# routev9_1.net
KiCad netlist of a schematic drawn in EAGLE
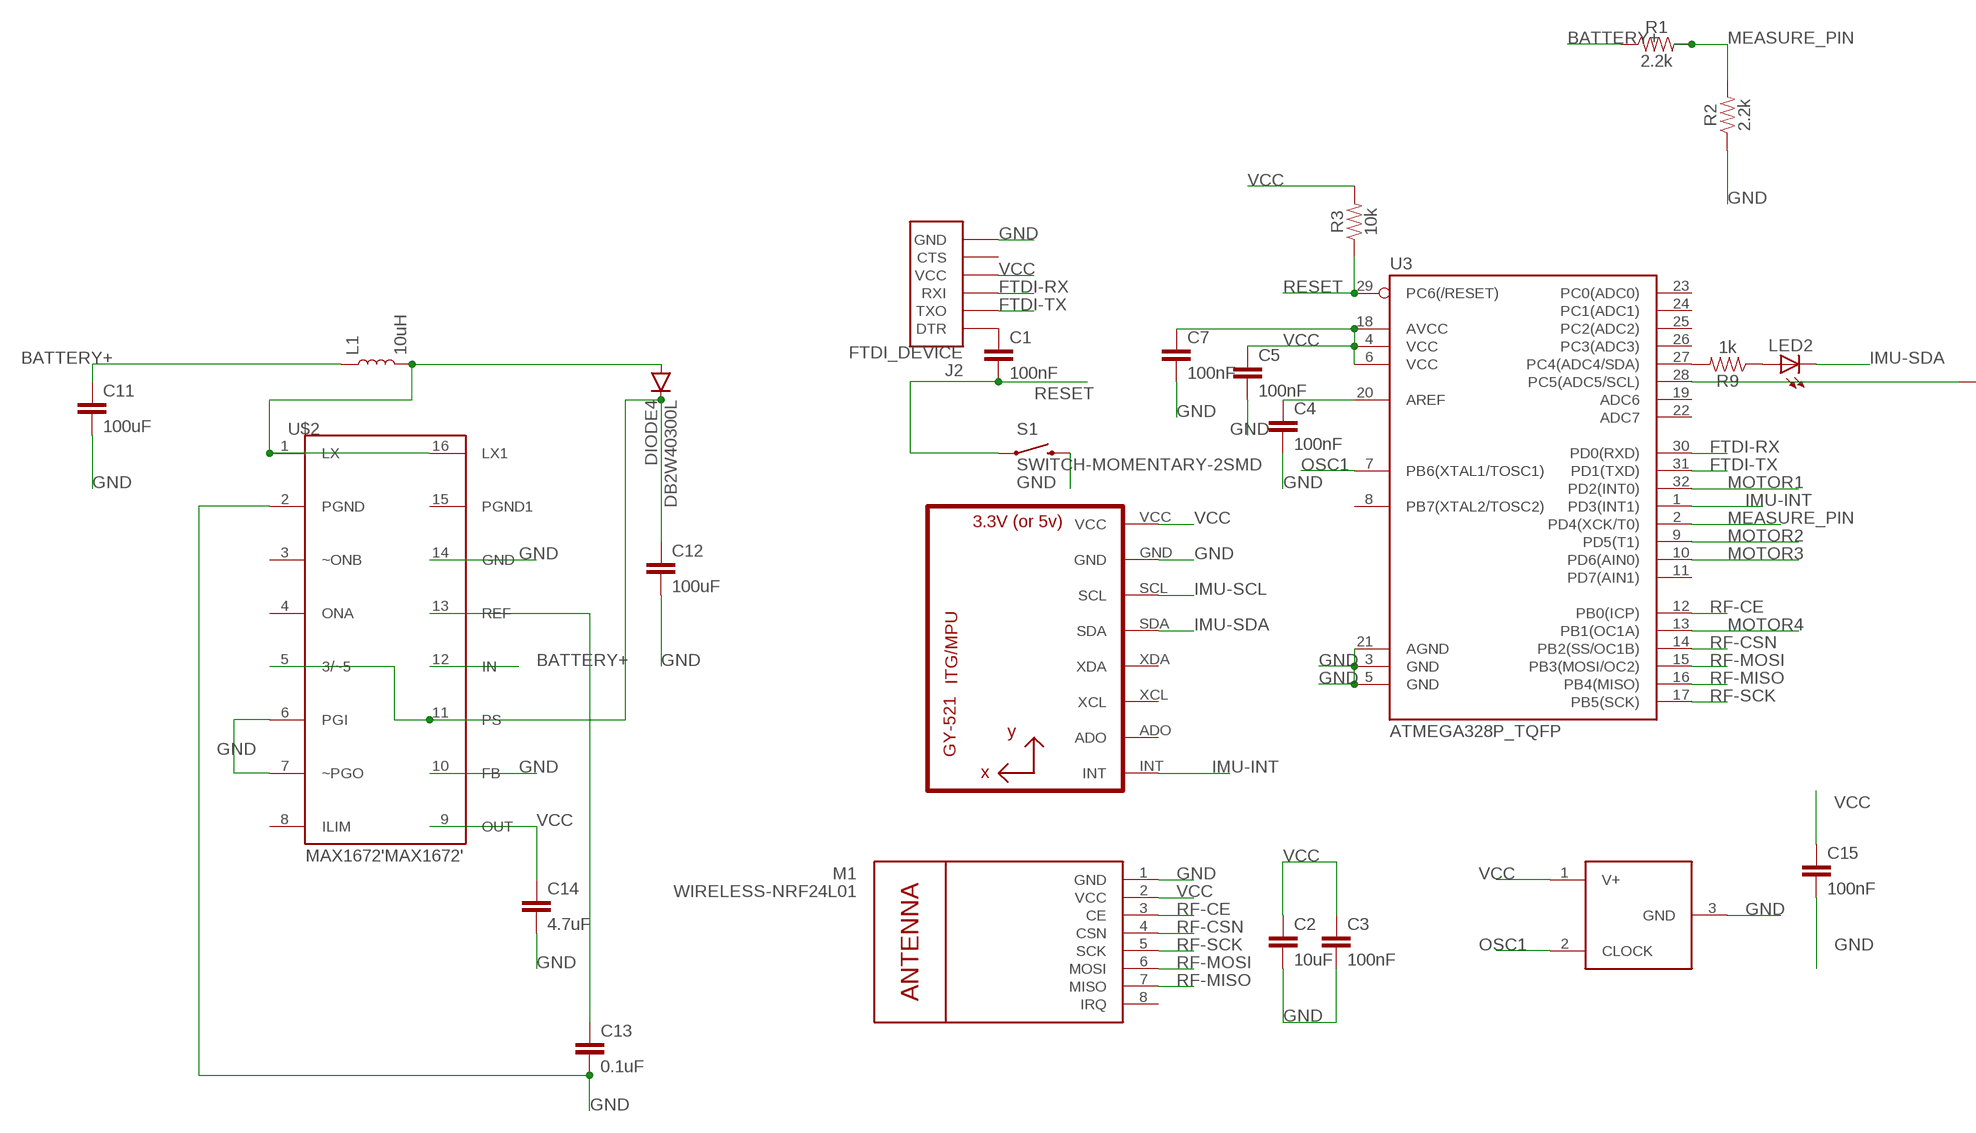
[diagram p0: schematic, sheet 1, part 1 of 2]
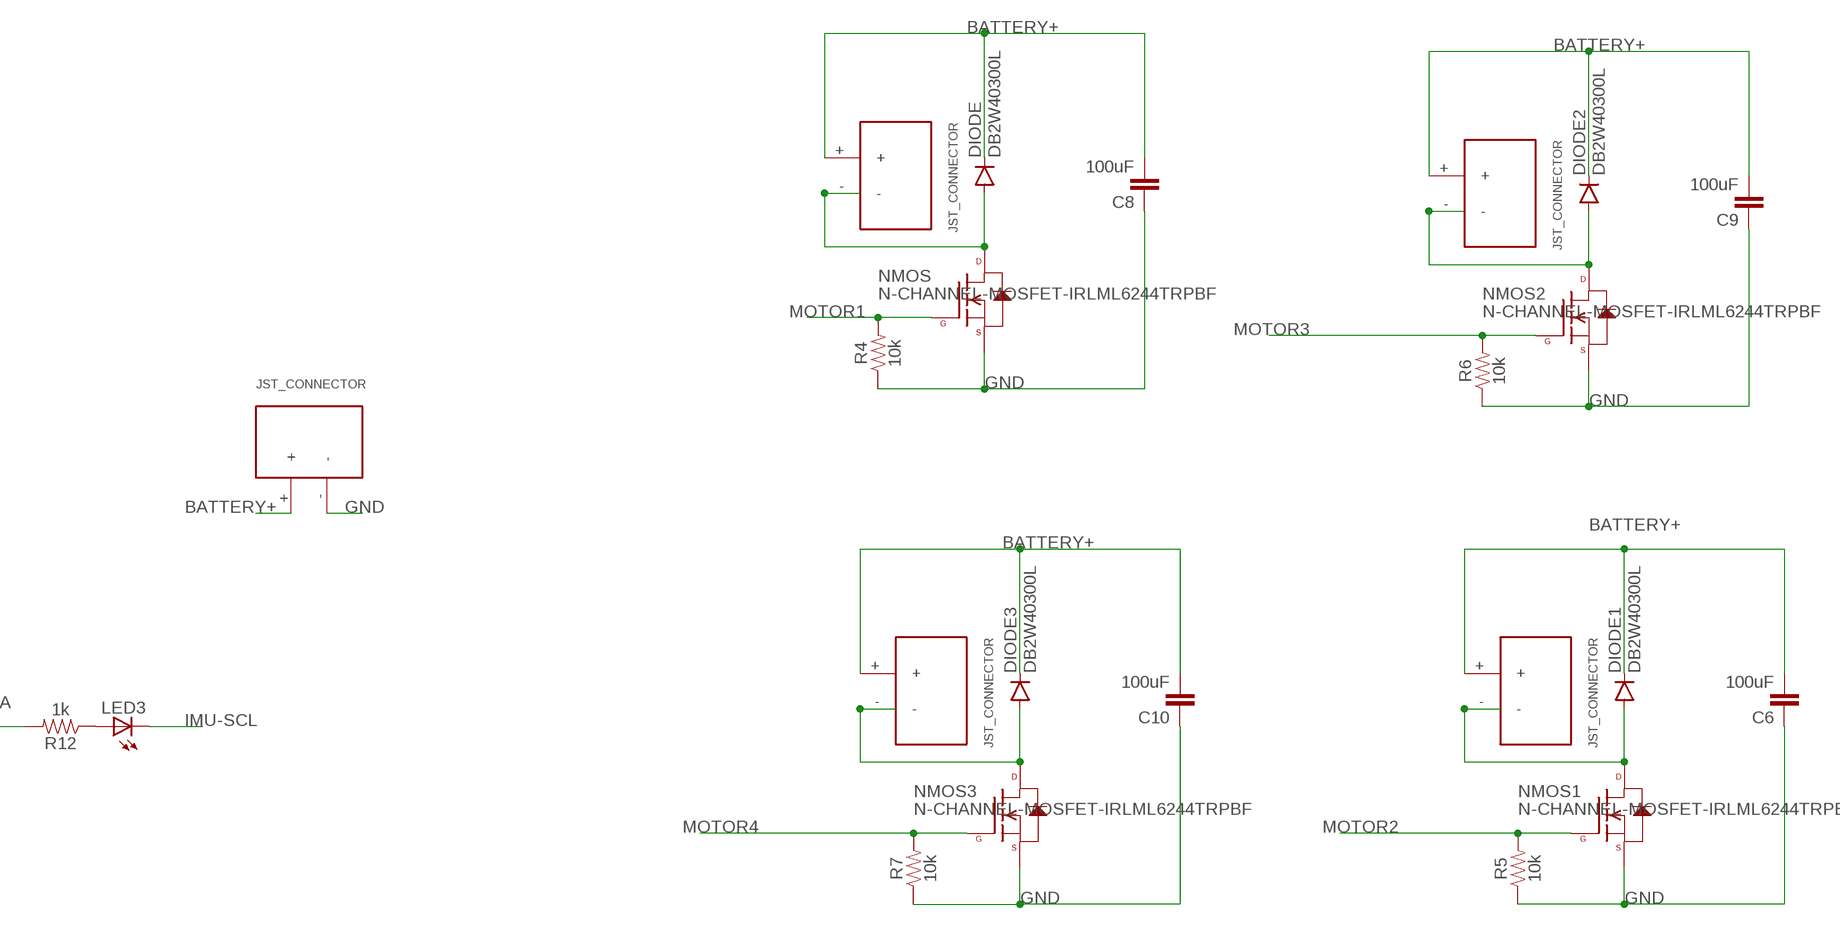
[diagram p1: schematic, sheet 1, part 2 of 2]

(export (version "E")
  (design (tool "Eeschema 10.0.6"))
  (components
    (comp (ref "AXR1")
      (value "MAX7375")
      (footprint "eagle-import:SC70-3L")
      (libsource (lib "eagle-import") (part "MAX7375"))
    )
    (comp (ref "C1")
      (value "100nF")
      (footprint "eagle-import:0603-CAP")
      (libsource (lib "eagle-import") (part "0.1UF-25V(+80/-20%)(0603)"))
    )
    (comp (ref "C2")
      (value "10uF")
      (footprint "eagle-import:0603-CAP")
      (libsource (lib "eagle-import") (part "CAP0603-CAP"))
    )
    (comp (ref "C3")
      (value "100nF")
      (footprint "eagle-import:0603-CAP")
      (libsource (lib "eagle-import") (part "CAP0603-CAP"))
    )
    (comp (ref "C4")
      (value "100nF")
      (footprint "eagle-import:0603-CAP")
      (libsource (lib "eagle-import") (part "CAP0603-CAP"))
    )
    (comp (ref "C5")
      (value "100nF")
      (footprint "eagle-import:0603-CAP")
      (libsource (lib "eagle-import") (part "CAP0603-CAP"))
    )
    (comp (ref "C6")
      (value "100uF")
      (footprint "eagle-import:0603-CAP")
      (libsource (lib "eagle-import") (part "CAP0603-CAP"))
    )
    (comp (ref "C7")
      (value "100nF")
      (footprint "eagle-import:0603-CAP")
      (libsource (lib "eagle-import") (part "CAP0603-CAP"))
    )
    (comp (ref "C8")
      (value "100uF")
      (footprint "eagle-import:0603-CAP")
      (libsource (lib "eagle-import") (part "CAP0603-CAP"))
    )
    (comp (ref "C9")
      (value "100uF")
      (footprint "eagle-import:0603-CAP")
      (libsource (lib "eagle-import") (part "CAP0603-CAP"))
    )
    (comp (ref "C10")
      (value "100uF")
      (footprint "eagle-import:0603-CAP")
      (libsource (lib "eagle-import") (part "CAP0603-CAP"))
    )
    (comp (ref "C11")
      (value "100uF")
      (footprint "eagle-import:0603-CAP")
      (libsource (lib "eagle-import") (part "CAP0603-CAP"))
    )
    (comp (ref "C12")
      (value "100uF")
      (footprint "eagle-import:0603-CAP")
      (libsource (lib "eagle-import") (part "CAP0603-CAP"))
    )
    (comp (ref "C13")
      (value "0.1uF")
      (footprint "eagle-import:0603-CAP")
      (libsource (lib "eagle-import") (part "CAP0603-CAP"))
    )
    (comp (ref "C14")
      (value "4.7uF")
      (footprint "eagle-import:0603-CAP")
      (libsource (lib "eagle-import") (part "CAP0603-CAP"))
    )
    (comp (ref "C15")
      (value "100nF")
      (footprint "eagle-import:0603-CAP")
      (libsource (lib "eagle-import") (part "0.1UF-25V(+80/-20%)(0603)"))
    )
    (comp (ref "DIODE")
      (value "DB2W40300L")
      (footprint "eagle-import:MINI2-F3-B")
      (libsource (lib "eagle-import") (part "DB2W40300L"))
    )
    (comp (ref "DIODE1")
      (value "DB2W40300L")
      (footprint "eagle-import:MINI2-F3-B")
      (libsource (lib "eagle-import") (part "DB2W40300L"))
    )
    (comp (ref "DIODE2")
      (value "DB2W40300L")
      (footprint "eagle-import:MINI2-F3-B")
      (libsource (lib "eagle-import") (part "DB2W40300L"))
    )
    (comp (ref "DIODE3")
      (value "DB2W40300L")
      (footprint "eagle-import:MINI2-F3-B")
      (libsource (lib "eagle-import") (part "DB2W40300L"))
    )
    (comp (ref "DIODE4")
      (value "DB2W40300L")
      (footprint "eagle-import:MINI2-F3-B")
      (libsource (lib "eagle-import") (part "DB2W40300L"))
    )
    (comp (ref "J2")
      (value "FTDI_DEVICE")
      (footprint "eagle-import:FTDI_DEVICE_SIDE")
      (libsource (lib "eagle-import") (part "FTDI_DEVICE"))
    )
    (comp (ref "L1")
      (value "10uH")
      (footprint "eagle-import:0603")
      (libsource (lib "eagle-import") (part "INDUCTOR-0603-33NH"))
    )
    (comp (ref "LED2")
      (value "LED0603")
      (footprint "eagle-import:LED-0603")
      (libsource (lib "eagle-import") (part "LED0603"))
    )
    (comp (ref "LED3")
      (value "LED0603")
      (footprint "eagle-import:LED-0603")
      (libsource (lib "eagle-import") (part "LED0603"))
    )
    (comp (ref "M1")
      (value "WIRELESS-NRF24L01")
      (footprint "eagle-import:WIRELESS-NRF24L01")
      (libsource (lib "eagle-import") (part "WIRELESS-NRF24L01"))
    )
    (comp (ref "MOTOR")
      (value "JST_CONNECTOR_FEMALE")
      (footprint "eagle-import:JST_CONNECTOR_FEMALE")
      (libsource (lib "eagle-import") (part "JST_CONNECTOR_FEMALE"))
    )
    (comp (ref "MOTOR1")
      (value "JST_CONNECTOR_FEMALE")
      (footprint "eagle-import:JST_CONNECTOR_FEMALE")
      (libsource (lib "eagle-import") (part "JST_CONNECTOR_FEMALE"))
    )
    (comp (ref "MOTOR2")
      (value "JST_CONNECTOR_FEMALE")
      (footprint "eagle-import:JST_CONNECTOR_FEMALE")
      (libsource (lib "eagle-import") (part "JST_CONNECTOR_FEMALE"))
    )
    (comp (ref "MOTOR3")
      (value "JST_CONNECTOR_FEMALE")
      (footprint "eagle-import:JST_CONNECTOR_FEMALE")
      (libsource (lib "eagle-import") (part "JST_CONNECTOR_FEMALE"))
    )
    (comp (ref "NMOS")
      (value "N-CHANNEL-MOSFET-IRLML6244TRPBF")
      (footprint "eagle-import:SOT23-3")
      (libsource (lib "eagle-import") (part "N-CHANNEL-MOSFET-IRLML6244TRPBF"))
    )
    (comp (ref "NMOS1")
      (value "N-CHANNEL-MOSFET-IRLML6244TRPBF")
      (footprint "eagle-import:SOT23-3")
      (libsource (lib "eagle-import") (part "N-CHANNEL-MOSFET-IRLML6244TRPBF"))
    )
    (comp (ref "NMOS2")
      (value "N-CHANNEL-MOSFET-IRLML6244TRPBF")
      (footprint "eagle-import:SOT23-3")
      (libsource (lib "eagle-import") (part "N-CHANNEL-MOSFET-IRLML6244TRPBF"))
    )
    (comp (ref "NMOS3")
      (value "N-CHANNEL-MOSFET-IRLML6244TRPBF")
      (footprint "eagle-import:SOT23-3")
      (libsource (lib "eagle-import") (part "N-CHANNEL-MOSFET-IRLML6244TRPBF"))
    )
    (comp (ref "R1")
      (value "2.2k")
      (footprint "eagle-import:0603")
      (libsource (lib "eagle-import") (part "2.2KOHM-0603-1/10W-1%"))
    )
    (comp (ref "R2")
      (value "2.2k")
      (footprint "eagle-import:0603")
      (libsource (lib "eagle-import") (part "2.2KOHM-0603-1/10W-1%"))
    )
    (comp (ref "R3")
      (value "10k")
      (footprint "eagle-import:0603")
      (libsource (lib "eagle-import") (part "2.2KOHM-0603-1/10W-1%"))
    )
    (comp (ref "R4")
      (value "10k")
      (footprint "eagle-import:0603")
      (libsource (lib "eagle-import") (part "2.2KOHM-0603-1/10W-1%"))
    )
    (comp (ref "R5")
      (value "10k")
      (footprint "eagle-import:0603")
      (libsource (lib "eagle-import") (part "2.2KOHM-0603-1/10W-1%"))
    )
    (comp (ref "R6")
      (value "10k")
      (footprint "eagle-import:0603")
      (libsource (lib "eagle-import") (part "2.2KOHM-0603-1/10W-1%"))
    )
    (comp (ref "R7")
      (value "10k")
      (footprint "eagle-import:0603")
      (libsource (lib "eagle-import") (part "2.2KOHM-0603-1/10W-1%"))
    )
    (comp (ref "R9")
      (value "1k")
      (footprint "eagle-import:0603")
      (libsource (lib "eagle-import") (part "2.2KOHM-0603-1/10W-1%"))
    )
    (comp (ref "R12")
      (value "1k")
      (footprint "eagle-import:0603")
      (libsource (lib "eagle-import") (part "2.2KOHM-0603-1/10W-1%"))
    )
    (comp (ref "S1")
      (value "SWITCH-MOMENTARY-2SMD")
      (footprint "eagle-import:TACTILE-SWITCH-SMD")
      (libsource (lib "eagle-import") (part "SWITCH-MOMENTARY-2SMD"))
    )
    (comp (ref "U$1")
      (value "JST_CONNECTOR_FEMALE")
      (footprint "eagle-import:JST_CONNECTOR_FEMALE")
      (libsource (lib "eagle-import") (part "JST_CONNECTOR_FEMALE"))
    )
    (comp (ref "U$2")
      (value "MAX1672'MAX1672'")
      (footprint "eagle-import:21-0055H_16")
      (libsource (lib "eagle-import") (part "MAX1672'MAX1672'"))
    )
    (comp (ref "U2")
      (value "GY-521MPU6050")
      (footprint "eagle-import:GY-521")
      (libsource (lib "eagle-import") (part "GY-521MPU6050"))
    )
    (comp (ref "U3")
      (value "ATMEGA328P_TQFP")
      (footprint "eagle-import:TQFP32-08")
      (libsource (lib "eagle-import") (part "ATMEGA328P_TQFP"))
    )
  )
  (nets
    (net (code "1") (name "BATTERY+") (class "Default")
      (node (ref "C10") (pin "2") (pinfunction "2_2") (pintype "passive"))
      (node (ref "C11") (pin "1") (pinfunction "1_1") (pintype "passive"))
      (node (ref "C6") (pin "2") (pinfunction "2_2") (pintype "passive"))
      (node (ref "C8") (pin "2") (pinfunction "2_2") (pintype "passive"))
      (node (ref "C9") (pin "2") (pinfunction "2_2") (pintype "passive"))
      (node (ref "DIODE") (pin "NEG") (pinfunction "GPIN_NEG") (pintype "passive"))
      (node (ref "DIODE1") (pin "NEG") (pinfunction "GPIN_NEG") (pintype "passive"))
      (node (ref "DIODE2") (pin "NEG") (pinfunction "GPIN_NEG") (pintype "passive"))
      (node (ref "DIODE3") (pin "NEG") (pinfunction "GPIN_NEG") (pintype "passive"))
      (node (ref "L1") (pin "1") (pinfunction "1_1") (pintype "passive"))
      (node (ref "MOTOR") (pin "+") (pinfunction "+_+") (pintype "bidirectional"))
      (node (ref "MOTOR1") (pin "+") (pinfunction "+_+") (pintype "bidirectional"))
      (node (ref "MOTOR2") (pin "+") (pinfunction "+_+") (pintype "bidirectional"))
      (node (ref "MOTOR3") (pin "+") (pinfunction "+_+") (pintype "bidirectional"))
      (node (ref "R1") (pin "1") (pinfunction "1_1") (pintype "passive"))
      (node (ref "U$1") (pin "+") (pinfunction "+_+") (pintype "bidirectional"))
      (node (ref "U$2") (pin "12") (pinfunction "IN_12") (pintype "bidirectional"))
    )
    (net (code "2") (name "FTDI-RX") (class "Default")
      (node (ref "J2") (pin "P$3") (pinfunction "RXI_P$3") (pintype "bidirectional"))
      (node (ref "U3") (pin "30") (pinfunction "PD0(RXD)_30") (pintype "bidirectional"))
    )
    (net (code "3") (name "FTDI-TX") (class "Default")
      (node (ref "J2") (pin "P$2") (pinfunction "TXO_P$2") (pintype "bidirectional"))
      (node (ref "U3") (pin "31") (pinfunction "PD1(TXD)_31") (pintype "bidirectional"))
    )
    (net (code "4") (name "GND") (class "Default")
      (node (ref "AXR1") (pin "3") (pinfunction "GND_3") (pintype "bidirectional"))
      (node (ref "C10") (pin "1") (pinfunction "1_1") (pintype "passive"))
      (node (ref "C11") (pin "2") (pinfunction "2_2") (pintype "passive"))
      (node (ref "C12") (pin "2") (pinfunction "2_2") (pintype "passive"))
      (node (ref "C13") (pin "2") (pinfunction "2_2") (pintype "passive"))
      (node (ref "C14") (pin "2") (pinfunction "2_2") (pintype "passive"))
      (node (ref "C15") (pin "2") (pinfunction "2_2") (pintype "passive"))
      (node (ref "C2") (pin "2") (pinfunction "2_2") (pintype "passive"))
      (node (ref "C3") (pin "2") (pinfunction "2_2") (pintype "passive"))
      (node (ref "C4") (pin "2") (pinfunction "2_2") (pintype "passive"))
      (node (ref "C5") (pin "2") (pinfunction "2_2") (pintype "passive"))
      (node (ref "C6") (pin "1") (pinfunction "1_1") (pintype "passive"))
      (node (ref "C7") (pin "2") (pinfunction "2_2") (pintype "passive"))
      (node (ref "C8") (pin "1") (pinfunction "1_1") (pintype "passive"))
      (node (ref "C9") (pin "1") (pinfunction "1_1") (pintype "passive"))
      (node (ref "J2") (pin "P$6") (pinfunction "GND_P$6") (pintype "bidirectional"))
      (node (ref "M1") (pin "1") (pinfunction "GND_1") (pintype "power_in"))
      (node (ref "NMOS") (pin "2") (pinfunction "S_2") (pintype "passive"))
      (node (ref "NMOS1") (pin "2") (pinfunction "S_2") (pintype "passive"))
      (node (ref "NMOS2") (pin "2") (pinfunction "S_2") (pintype "passive"))
      (node (ref "NMOS3") (pin "2") (pinfunction "S_2") (pintype "passive"))
      (node (ref "R2") (pin "1") (pinfunction "1_1") (pintype "passive"))
      (node (ref "R4") (pin "1") (pinfunction "1_1") (pintype "passive"))
      (node (ref "R5") (pin "1") (pinfunction "1_1") (pintype "passive"))
      (node (ref "R6") (pin "1") (pinfunction "1_1") (pintype "passive"))
      (node (ref "R7") (pin "1") (pinfunction "1_1") (pintype "passive"))
      (node (ref "S1") (pin "3") (pinfunction "2_3") (pintype "passive"))
      (node (ref "U$1") (pin "-") (pinfunction "-_-") (pintype "bidirectional"))
      (node (ref "U$2") (pin "10") (pinfunction "FB_10") (pintype "bidirectional"))
      (node (ref "U$2") (pin "14") (pinfunction "GND_14") (pintype "bidirectional"))
      (node (ref "U$2") (pin "2") (pinfunction "PGND_2") (pintype "bidirectional"))
      (node (ref "U$2") (pin "6") (pinfunction "PGI_6") (pintype "bidirectional"))
      (node (ref "U$2") (pin "7") (pinfunction "~{PGO}_7") (pintype "bidirectional"))
      (node (ref "U2") (pin "GND") (pinfunction "GND_GND") (pintype "bidirectional"))
      (node (ref "U3") (pin "21") (pinfunction "AGND_21") (pintype "bidirectional"))
      (node (ref "U3") (pin "3") (pinfunction "GND_3") (pintype "bidirectional"))
      (node (ref "U3") (pin "5") (pinfunction "GND_5") (pintype "bidirectional"))
    )
    (net (code "5") (name "IMU-INT") (class "Default")
      (node (ref "U2") (pin "INT") (pinfunction "INT_INT") (pintype "bidirectional"))
      (node (ref "U3") (pin "1") (pinfunction "PD3(INT1)_1") (pintype "bidirectional"))
    )
    (net (code "6") (name "IMU-SCL") (class "Default")
      (node (ref "LED3") (pin "C") (pinfunction "C_C") (pintype "passive"))
      (node (ref "U2") (pin "SCL") (pinfunction "SCL_SCL") (pintype "bidirectional"))
    )
    (net (code "7") (name "IMU-SDA") (class "Default")
      (node (ref "LED2") (pin "C") (pinfunction "C_C") (pintype "passive"))
      (node (ref "U2") (pin "SDA") (pinfunction "SDA_SDA") (pintype "bidirectional"))
    )
    (net (code "8") (name "MEASURE_PIN") (class "Default")
      (node (ref "R1") (pin "2") (pinfunction "2_2") (pintype "passive"))
      (node (ref "R2") (pin "2") (pinfunction "2_2") (pintype "passive"))
      (node (ref "U3") (pin "2") (pinfunction "PD4(XCK/T0)_2") (pintype "bidirectional"))
    )
    (net (code "9") (name "MOTOR1") (class "Default")
      (node (ref "NMOS") (pin "1") (pinfunction "G_1") (pintype "passive"))
      (node (ref "R4") (pin "2") (pinfunction "2_2") (pintype "passive"))
      (node (ref "U3") (pin "32") (pinfunction "PD2(INT0)_32") (pintype "bidirectional"))
    )
    (net (code "10") (name "MOTOR2") (class "Default")
      (node (ref "NMOS1") (pin "1") (pinfunction "G_1") (pintype "passive"))
      (node (ref "R5") (pin "2") (pinfunction "2_2") (pintype "passive"))
      (node (ref "U3") (pin "9") (pinfunction "PD5(T1)_9") (pintype "bidirectional"))
    )
    (net (code "11") (name "MOTOR3") (class "Default")
      (node (ref "NMOS2") (pin "1") (pinfunction "G_1") (pintype "passive"))
      (node (ref "R6") (pin "2") (pinfunction "2_2") (pintype "passive"))
      (node (ref "U3") (pin "10") (pinfunction "PD6(AIN0)_10") (pintype "bidirectional"))
    )
    (net (code "12") (name "MOTOR4") (class "Default")
      (node (ref "NMOS3") (pin "1") (pinfunction "G_1") (pintype "passive"))
      (node (ref "R7") (pin "2") (pinfunction "2_2") (pintype "passive"))
      (node (ref "U3") (pin "13") (pinfunction "PB1(OC1A)_13") (pintype "bidirectional"))
    )
    (net (code "13") (name "Net-(DIODE-PPIN)") (class "Default")
      (node (ref "DIODE") (pin "POS") (pinfunction "PPIN_POS") (pintype "passive"))
      (node (ref "MOTOR") (pin "-") (pinfunction "-_-") (pintype "bidirectional"))
      (node (ref "NMOS") (pin "3") (pinfunction "D_3") (pintype "passive"))
    )
    (net (code "14") (name "Net-(DIODE1-PPIN)") (class "Default")
      (node (ref "DIODE1") (pin "POS") (pinfunction "PPIN_POS") (pintype "passive"))
      (node (ref "MOTOR1") (pin "-") (pinfunction "-_-") (pintype "bidirectional"))
      (node (ref "NMOS1") (pin "3") (pinfunction "D_3") (pintype "passive"))
    )
    (net (code "15") (name "Net-(DIODE2-PPIN)") (class "Default")
      (node (ref "DIODE2") (pin "POS") (pinfunction "PPIN_POS") (pintype "passive"))
      (node (ref "MOTOR2") (pin "-") (pinfunction "-_-") (pintype "bidirectional"))
      (node (ref "NMOS2") (pin "3") (pinfunction "D_3") (pintype "passive"))
    )
    (net (code "16") (name "Net-(DIODE3-PPIN)") (class "Default")
      (node (ref "DIODE3") (pin "POS") (pinfunction "PPIN_POS") (pintype "passive"))
      (node (ref "MOTOR3") (pin "-") (pinfunction "-_-") (pintype "bidirectional"))
      (node (ref "NMOS3") (pin "3") (pinfunction "D_3") (pintype "passive"))
    )
    (net (code "17") (name "Net-(DIODE4-GPIN)") (class "Default")
      (node (ref "C12") (pin "1") (pinfunction "1_1") (pintype "passive"))
      (node (ref "DIODE4") (pin "NEG") (pinfunction "GPIN_NEG") (pintype "passive"))
      (node (ref "U$2") (pin "11") (pinfunction "PS_11") (pintype "bidirectional"))
      (node (ref "U$2") (pin "5") (pinfunction "3/~{5}_5") (pintype "bidirectional"))
    )
    (net (code "18") (name "Net-(DIODE4-PPIN)") (class "Default")
      (node (ref "DIODE4") (pin "POS") (pinfunction "PPIN_POS") (pintype "passive"))
      (node (ref "L1") (pin "2") (pinfunction "2_2") (pintype "passive"))
      (node (ref "U$2") (pin "1") (pinfunction "LX_1") (pintype "bidirectional"))
      (node (ref "U$2") (pin "16") (pinfunction "LX1_16") (pintype "bidirectional"))
    )
    (net (code "19") (name "Net-(J2-DTR)") (class "Default")
      (node (ref "C1") (pin "1") (pinfunction "1_1") (pintype "passive"))
      (node (ref "J2") (pin "P$1") (pinfunction "DTR_P$1") (pintype "bidirectional"))
    )
    (net (code "20") (name "Net-(LED2-PadA)") (class "Default")
      (node (ref "LED2") (pin "A") (pinfunction "A_A") (pintype "passive"))
      (node (ref "R9") (pin "1") (pinfunction "1_1") (pintype "passive"))
    )
    (net (code "21") (name "Net-(LED3-PadA)") (class "Default")
      (node (ref "LED3") (pin "A") (pinfunction "A_A") (pintype "passive"))
      (node (ref "R12") (pin "1") (pinfunction "1_1") (pintype "passive"))
    )
    (net (code "22") (name "Net-(U$2-REF)") (class "Default")
      (node (ref "C13") (pin "1") (pinfunction "1_1") (pintype "passive"))
      (node (ref "U$2") (pin "13") (pinfunction "REF_13") (pintype "bidirectional"))
    )
    (net (code "23") (name "Net-(U3-AREF)") (class "Default")
      (node (ref "C4") (pin "1") (pinfunction "1_1") (pintype "passive"))
      (node (ref "U3") (pin "20") (pinfunction "AREF_20") (pintype "bidirectional"))
    )
    (net (code "24") (name "Net-(U3-PC4(ADC4{slash}SDA))") (class "Default")
      (node (ref "R9") (pin "2") (pinfunction "2_2") (pintype "passive"))
      (node (ref "U3") (pin "27") (pinfunction "PC4(ADC4/SDA)_27") (pintype "bidirectional"))
    )
    (net (code "25") (name "Net-(U3-PC5(ADC5{slash}SCL))") (class "Default")
      (node (ref "R12") (pin "2") (pinfunction "2_2") (pintype "passive"))
      (node (ref "U3") (pin "28") (pinfunction "PC5(ADC5/SCL)_28") (pintype "bidirectional"))
    )
    (net (code "26") (name "OSC1") (class "Default")
      (node (ref "AXR1") (pin "2") (pinfunction "CLOCK_2") (pintype "bidirectional"))
      (node (ref "U3") (pin "7") (pinfunction "PB6(XTAL1/TOSC1)_7") (pintype "bidirectional"))
    )
    (net (code "27") (name "RESET") (class "Default")
      (node (ref "C1") (pin "2") (pinfunction "2_2") (pintype "passive"))
      (node (ref "R3") (pin "1") (pinfunction "1_1") (pintype "passive"))
      (node (ref "S1") (pin "1") (pinfunction "1_1") (pintype "passive"))
      (node (ref "U3") (pin "29") (pinfunction "PC6(/RESET)_29") (pintype "bidirectional"))
    )
    (net (code "28") (name "RF-CE") (class "Default")
      (node (ref "M1") (pin "3") (pinfunction "CE_3") (pintype "bidirectional"))
      (node (ref "U3") (pin "12") (pinfunction "PB0(ICP)_12") (pintype "bidirectional"))
    )
    (net (code "29") (name "RF-CSN") (class "Default")
      (node (ref "M1") (pin "4") (pinfunction "CSN_4") (pintype "bidirectional"))
      (node (ref "U3") (pin "14") (pinfunction "PB2(SS/OC1B)_14") (pintype "bidirectional"))
    )
    (net (code "30") (name "RF-MISO") (class "Default")
      (node (ref "M1") (pin "7") (pinfunction "MISO_7") (pintype "bidirectional"))
      (node (ref "U3") (pin "16") (pinfunction "PB4(MISO)_16") (pintype "bidirectional"))
    )
    (net (code "31") (name "RF-MOSI") (class "Default")
      (node (ref "M1") (pin "6") (pinfunction "MOSI_6") (pintype "bidirectional"))
      (node (ref "U3") (pin "15") (pinfunction "PB3(MOSI/OC2)_15") (pintype "bidirectional"))
    )
    (net (code "32") (name "RF-SCK") (class "Default")
      (node (ref "M1") (pin "5") (pinfunction "SCK_5") (pintype "bidirectional"))
      (node (ref "U3") (pin "17") (pinfunction "PB5(SCK)_17") (pintype "bidirectional"))
    )
    (net (code "33") (name "VCC") (class "Default")
      (node (ref "AXR1") (pin "1") (pinfunction "V+_1") (pintype "bidirectional"))
      (node (ref "C14") (pin "1") (pinfunction "1_1") (pintype "passive"))
      (node (ref "C15") (pin "1") (pinfunction "1_1") (pintype "passive"))
      (node (ref "C2") (pin "1") (pinfunction "1_1") (pintype "passive"))
      (node (ref "C3") (pin "1") (pinfunction "1_1") (pintype "passive"))
      (node (ref "C5") (pin "1") (pinfunction "1_1") (pintype "passive"))
      (node (ref "C7") (pin "1") (pinfunction "1_1") (pintype "passive"))
      (node (ref "J2") (pin "P$4") (pinfunction "VCC_P$4") (pintype "bidirectional"))
      (node (ref "M1") (pin "2") (pinfunction "VCC_2") (pintype "power_in"))
      (node (ref "R3") (pin "2") (pinfunction "2_2") (pintype "passive"))
      (node (ref "U$2") (pin "9") (pinfunction "OUT_9") (pintype "bidirectional"))
      (node (ref "U2") (pin "VCC") (pinfunction "VCC_VCC") (pintype "bidirectional"))
      (node (ref "U3") (pin "18") (pinfunction "AVCC_18") (pintype "bidirectional"))
      (node (ref "U3") (pin "4") (pinfunction "VCC_4") (pintype "bidirectional"))
      (node (ref "U3") (pin "6") (pinfunction "VCC_6") (pintype "bidirectional"))
    )
    (net (code "34") (name "unconnected-(J2-CTS-PadP$5)") (class "Default")
      (node (ref "J2") (pin "P$5") (pinfunction "CTS_P$5") (pintype "bidirectional"))
    )
    (net (code "35") (name "unconnected-(M1-IRQ-Pad8)") (class "Default")
      (node (ref "M1") (pin "8") (pinfunction "IRQ_8") (pintype "bidirectional"))
    )
    (net (code "36") (name "unconnected-(U$2-ILIM-Pad8)") (class "Default")
      (node (ref "U$2") (pin "8") (pinfunction "ILIM_8") (pintype "bidirectional"))
    )
    (net (code "37") (name "unconnected-(U$2-ONA-Pad4)") (class "Default")
      (node (ref "U$2") (pin "4") (pinfunction "ONA_4") (pintype "bidirectional"))
    )
    (net (code "38") (name "unconnected-(U$2-PGND1-Pad15)") (class "Default")
      (node (ref "U$2") (pin "15") (pinfunction "PGND1_15") (pintype "bidirectional"))
    )
    (net (code "39") (name "unconnected-(U$2-~{ONB}-Pad3)") (class "Default")
      (node (ref "U$2") (pin "3") (pinfunction "~{ONB}_3") (pintype "bidirectional"))
    )
    (net (code "40") (name "unconnected-(U2-PadADO)") (class "Default")
      (node (ref "U2") (pin "ADO") (pinfunction "ADO_ADO") (pintype "bidirectional"))
    )
    (net (code "41") (name "unconnected-(U2-PadXCL)") (class "Default")
      (node (ref "U2") (pin "XCL") (pinfunction "XCL_XCL") (pintype "bidirectional"))
    )
    (net (code "42") (name "unconnected-(U2-PadXDA)") (class "Default")
      (node (ref "U2") (pin "XDA") (pinfunction "XDA_XDA") (pintype "bidirectional"))
    )
    (net (code "43") (name "unconnected-(U3-ADC6-Pad19)") (class "Default")
      (node (ref "U3") (pin "19") (pinfunction "ADC6_19") (pintype "bidirectional"))
    )
    (net (code "44") (name "unconnected-(U3-ADC7-Pad22)") (class "Default")
      (node (ref "U3") (pin "22") (pinfunction "ADC7_22") (pintype "bidirectional"))
    )
    (net (code "45") (name "unconnected-(U3-PB7(XTAL2{slash}TOSC2)-Pad8)") (class "Default")
      (node (ref "U3") (pin "8") (pinfunction "PB7(XTAL2/TOSC2)_8") (pintype "bidirectional"))
    )
    (net (code "46") (name "unconnected-(U3-PC0(ADC0)-Pad23)") (class "Default")
      (node (ref "U3") (pin "23") (pinfunction "PC0(ADC0)_23") (pintype "bidirectional"))
    )
    (net (code "47") (name "unconnected-(U3-PC1(ADC1)-Pad24)") (class "Default")
      (node (ref "U3") (pin "24") (pinfunction "PC1(ADC1)_24") (pintype "bidirectional"))
    )
    (net (code "48") (name "unconnected-(U3-PC2(ADC2)-Pad25)") (class "Default")
      (node (ref "U3") (pin "25") (pinfunction "PC2(ADC2)_25") (pintype "bidirectional"))
    )
    (net (code "49") (name "unconnected-(U3-PC3(ADC3)-Pad26)") (class "Default")
      (node (ref "U3") (pin "26") (pinfunction "PC3(ADC3)_26") (pintype "bidirectional"))
    )
    (net (code "50") (name "unconnected-(U3-PD7(AIN1)-Pad11)") (class "Default")
      (node (ref "U3") (pin "11") (pinfunction "PD7(AIN1)_11") (pintype "bidirectional"))
    )
  )
)
